# Arduino_mini.net
KiCad netlist of a schematic drawn in Altium Designer
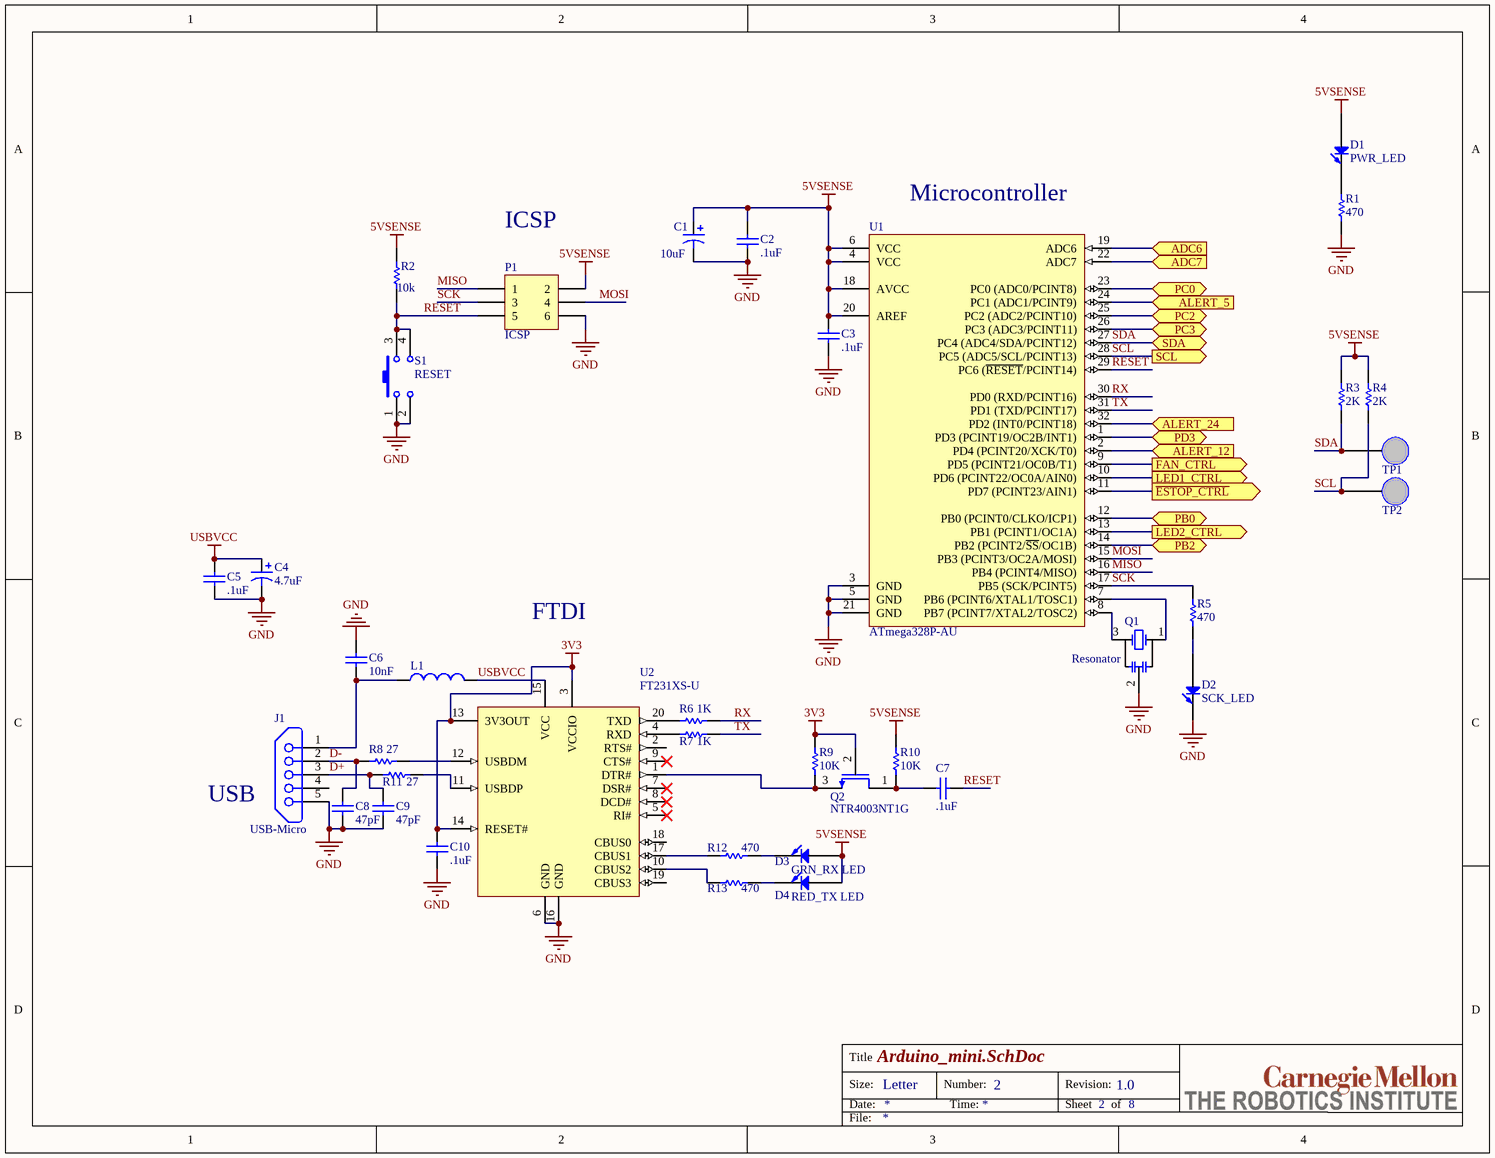
[diagram p0: Arduino_mini.SchDoc]

(export (version "E")
  (design (tool "Eeschema 10.0.6"))
  (components
    (comp (ref "C1")
      (value "10uF")
      (footprint "CAPC2012N")
      (description "Polarized Capacitor (Radial)")
      (fields
        (field (name "MANUFACTURER") "AVX Corporation")
        (field (name "MANUFACTURER PART NUMBER") "TACL106M010RTA")
        (field (name "PUBLISHER") "Altium Limited")
      )
      (libsource (lib "Miscellaneous Devices") (part "Cap Pol1"))
    )
    (comp (ref "C2")
      (value ".1uF")
      (footprint "CAPC1608N")
      (description "Capacitor (Semiconductor SIM Model)")
      (fields
        (field (name "MANUFACTURER") "Murata Electronics North America")
        (field (name "MANUFACTURER PART NUMBER") "GRM188R71C104KA01D")
        (field (name "PUBLISHER") "Altium Limited")
      )
      (libsource (lib "Miscellaneous Devices") (part "Cap Semi"))
    )
    (comp (ref "C3")
      (value ".1uF")
      (footprint "CAPC1608N")
      (description "Capacitor (Semiconductor SIM Model)")
      (fields
        (field (name "MANUFACTURER") "Murata Electronics North America")
        (field (name "MANUFACTURER PART NUMBER") "GRM188R71C104KA01D")
        (field (name "PUBLISHER") "Altium Limited")
      )
      (libsource (lib "Miscellaneous Devices") (part "Cap Semi"))
    )
    (comp (ref "C4")
      (value "4.7uF")
      (footprint "CAPC2012N")
      (description "Polarized Capacitor (Radial)")
      (fields
        (field (name "MANUFACTURER") "AVX Corporation")
        (field (name "MANUFACTURER PART NUMBER") "TACL106M010RTA")
        (field (name "PUBLISHER") "Altium Limited")
      )
      (libsource (lib "Miscellaneous Devices") (part "Cap Pol1"))
    )
    (comp (ref "C5")
      (value ".1uF")
      (footprint "CAPC1608N")
      (description "Capacitor (Semiconductor SIM Model)")
      (fields
        (field (name "MANUFACTURER") "Murata Electronics North America")
        (field (name "MANUFACTURER PART NUMBER") "GRM188R71C104KA01D")
        (field (name "PUBLISHER") "Altium Limited")
      )
      (libsource (lib "Miscellaneous Devices") (part "Cap Semi"))
    )
    (comp (ref "C6")
      (value "10nF")
      (footprint "CAPC1608N")
      (description "Capacitor (Semiconductor SIM Model)")
      (fields
        (field (name "MANUFACTURER") "Murata Electronics North America")
        (field (name "MANUFACTURER PART NUMBER") "GRM188R71C104KA01D")
        (field (name "PUBLISHER") "Altium Limited")
      )
      (libsource (lib "Miscellaneous Devices") (part "Cap Semi"))
    )
    (comp (ref "C7")
      (value ".1uF")
      (footprint "CAPC1608N")
      (description "Capacitor (Semiconductor SIM Model)")
      (fields
        (field (name "MANUFACTURER") "Murata Electronics North America")
        (field (name "MANUFACTURER PART NUMBER") "GRM188R71C104KA01D")
        (field (name "PUBLISHER") "Altium Limited")
      )
      (libsource (lib "Miscellaneous Devices") (part "Cap Semi"))
    )
    (comp (ref "C8")
      (value "47pF")
      (footprint "CAPC1608N")
      (description "Capacitor (Semiconductor SIM Model)")
      (fields
        (field (name "MANUFACTURER") "Murata Electronics North America")
        (field (name "MANUFACTURER PART NUMBER") "GRM188R71C104KA01D")
        (field (name "PUBLISHER") "Altium Limited")
      )
      (libsource (lib "Miscellaneous Devices") (part "Cap Semi"))
    )
    (comp (ref "C9")
      (value "47pF")
      (footprint "CAPC1608N")
      (description "Capacitor (Semiconductor SIM Model)")
      (fields
        (field (name "MANUFACTURER") "Murata Electronics North America")
        (field (name "MANUFACTURER PART NUMBER") "GRM188R71C104KA01D")
        (field (name "PUBLISHER") "Altium Limited")
      )
      (libsource (lib "Miscellaneous Devices") (part "Cap Semi"))
    )
    (comp (ref "C10")
      (value ".1uF")
      (footprint "CAPC1608N")
      (description "Capacitor (Semiconductor SIM Model)")
      (fields
        (field (name "MANUFACTURER") "Murata Electronics North America")
        (field (name "MANUFACTURER PART NUMBER") "GRM188R71C104KA01D")
        (field (name "PUBLISHER") "Altium Limited")
      )
      (libsource (lib "Miscellaneous Devices") (part "Cap Semi"))
    )
    (comp (ref "D1")
      (value "PWR_LED")
      (footprint "common:0603 - LED")
      (description "Green LED")
      (fields
        (field (name "MANUFACTURER") "Lite-On Inc.")
        (field (name "MANUFACTURER PART NUMBER") "LTST-C191TGKT")
      )
      (libsource (lib "common") (part "LED0"))
    )
    (comp (ref "D2")
      (value "SCK_LED")
      (footprint "common:0603 - LED")
      (description "Green LED")
      (fields
        (field (name "MANUFACTURER") "Lite-On Inc.")
        (field (name "MANUFACTURER PART NUMBER") "LTST-C191TBKT")
      )
      (libsource (lib "common") (part "LED0"))
    )
    (comp (ref "D3")
      (value "GRN_RX LED")
      (footprint "common:0603 - LED")
      (description "Green LED")
      (fields
        (field (name "MANUFACTURER") "Lite-On Inc")
        (field (name "MANUFACTURER PART NUMBER") "LTST-C191TGKT")
        (field (name "PUBLISHER") "Altium Limited")
      )
      (libsource (lib "common") (part "LED0"))
    )
    (comp (ref "D4")
      (value "RED_TX LED")
      (footprint "common:0603 - LED")
      (description "led")
      (fields
        (field (name "MANUFACTURER") "Lite-On Inc")
        (field (name "MANUFACTURER PART NUMBER") "LTST-C191KRKT")
        (field (name "PUBLISHER") "Altium Limited")
      )
      (libsource (lib "common") (part "LED0"))
    )
    (comp (ref "J1")
      (value "USB-Micro")
      (footprint "USB-Micro Type B")
      (description "USB-Micro Type B")
      (fields
        (field (name "MANUFACTURER") "Molex Inc")
        (field (name "MANUFACTURER PART NUMBER") "0675031020")
        (field (name "PUBLISHER") "Altium Limited")
      )
      (libsource (lib "common") (part "USB-Micro"))
    )
    (comp (ref "L1")
      (value "Ferrite Bead, USB_PWR")
      (footprint "INDC2012N")
      (description "Inductor")
      (fields
        (field (name "MANUFACTURER") "Laird-Signal Integrity Products")
        (field (name "MANUFACTURER PART NUMBER") "MI0805K400R-10")
        (field (name "PUBLISHER") "Altium Limited")
      )
      (libsource (lib "Miscellaneous Devices") (part "Inductor"))
    )
    (comp (ref "P1")
      (value "ICSP")
      (footprint "MHDR2X3-LOCK")
      (description "Header, 3-Pin, Dual row")
      (fields
        (field (name "MANUFACTURER") "Sullins Connector Solutions")
        (field (name "MANUFACTURER PART NUMBER") "LPPB032CFFN-RC")
      )
      (libsource (lib "Miscellaneous Connectors") (part "MHDR2X3"))
    )
    (comp (ref "Q1")
      (value "Resonator")
      (footprint "Resonator")
      (fields
        (field (name "MANUFACTURER") "Murata Electronics North America")
        (field (name "MANUFACTURER PART NUMBER") "CSTCE16M0V53-R0")
      )
      (libsource (lib "common") (part "Resonator"))
    )
    (comp (ref "Q2")
      (value "NTR4003NT1G")
      (footprint "SOT-23")
      (description "MOSFET N-CH 30V 500MA SOT-23")
      (fields (field (name "MANUFACTURER") "ON Semiconductor"))
      (libsource (lib "common") (part "NTR4003NT1G"))
    )
    (comp (ref "R1")
      (value "470")
      (footprint "RESC1608N")
      (description "Resistor")
      (fields
        (field (name "MANUFACTURER") "Rohm Semiconductor")
        (field (name "MANUFACTURER PART NUMBER") "MCR03ERTJ471")
        (field (name "PUBLISHER") "Altium Limited")
      )
      (libsource (lib "Miscellaneous Devices") (part "Res1"))
    )
    (comp (ref "R2")
      (value "10k")
      (footprint "RESC1608N")
      (description "Resistor")
      (fields
        (field (name "MANUFACTURER") "Yageo")
        (field (name "MANUFACTURER PART NUMBER") "RC0603JR-0710KL")
        (field (name "PUBLISHER") "Altium Limited")
      )
      (libsource (lib "Miscellaneous Devices") (part "Res1"))
    )
    (comp (ref "R3")
      (value "2K")
      (footprint "RESC1608N")
      (description "Resistor")
      (fields
        (field (name "MANUFACTURER") "Rohm Semiconductor")
        (field (name "MANUFACTURER PART NUMBER") "MCR03ERTJ471")
        (field (name "PUBLISHER") "Altium Limited")
      )
      (libsource (lib "Miscellaneous Devices") (part "Res1"))
    )
    (comp (ref "R4")
      (value "2K")
      (footprint "RESC1608N")
      (description "Resistor")
      (fields
        (field (name "MANUFACTURER") "Rohm Semiconductor")
        (field (name "MANUFACTURER PART NUMBER") "MCR03ERTJ471")
        (field (name "PUBLISHER") "Altium Limited")
      )
      (libsource (lib "Miscellaneous Devices") (part "Res1"))
    )
    (comp (ref "R5")
      (value "470")
      (footprint "RESC1608N")
      (description "Resistor")
      (fields
        (field (name "MANUFACTURER") "Rohm Semiconductor")
        (field (name "MANUFACTURER PART NUMBER") "MCR03ERTJ471")
        (field (name "PUBLISHER") "Altium Limited")
      )
      (libsource (lib "Miscellaneous Devices") (part "Res1"))
    )
    (comp (ref "R6")
      (value "1K")
      (footprint "RESC1608N")
      (description "Resistor")
      (fields
        (field (name "MANUFACTURER") "Rohm Semiconductor")
        (field (name "MANUFACTURER PART NUMBER") "MCR03ERTJ471")
        (field (name "PUBLISHER") "Altium Limited")
      )
      (libsource (lib "Miscellaneous Devices") (part "Res1"))
    )
    (comp (ref "R7")
      (value "1K")
      (footprint "RESC1608N")
      (description "Resistor")
      (fields
        (field (name "MANUFACTURER") "Rohm Semiconductor")
        (field (name "MANUFACTURER PART NUMBER") "MCR03ERTJ471")
        (field (name "PUBLISHER") "Altium Limited")
      )
      (libsource (lib "Miscellaneous Devices") (part "Res1"))
    )
    (comp (ref "R8")
      (value "27")
      (footprint "RESC1608N")
      (description "Resistor")
      (fields
        (field (name "MANUFACTURER") "Rohm Semiconductor")
        (field (name "MANUFACTURER PART NUMBER") "MCR03ERTJ471")
        (field (name "PUBLISHER") "Altium Limited")
      )
      (libsource (lib "Miscellaneous Devices") (part "Res1"))
    )
    (comp (ref "R9")
      (value "10K")
      (footprint "RESC1608N")
      (description "Resistor")
      (fields
        (field (name "MANUFACTURER") "Rohm Semiconductor")
        (field (name "MANUFACTURER PART NUMBER") "MCR03ERTJ471")
        (field (name "PUBLISHER") "Altium Limited")
      )
      (libsource (lib "Miscellaneous Devices") (part "Res1"))
    )
    (comp (ref "R10")
      (value "10K")
      (footprint "RESC1608N")
      (description "Resistor")
      (fields
        (field (name "MANUFACTURER") "Rohm Semiconductor")
        (field (name "MANUFACTURER PART NUMBER") "MCR03ERTJ471")
        (field (name "PUBLISHER") "Altium Limited")
      )
      (libsource (lib "Miscellaneous Devices") (part "Res1"))
    )
    (comp (ref "R11")
      (value "27")
      (footprint "RESC1608N")
      (description "Resistor")
      (fields
        (field (name "MANUFACTURER") "Rohm Semiconductor")
        (field (name "MANUFACTURER PART NUMBER") "MCR03ERTJ471")
        (field (name "PUBLISHER") "Altium Limited")
      )
      (libsource (lib "Miscellaneous Devices") (part "Res1"))
    )
    (comp (ref "R12")
      (value "470")
      (footprint "RESC1608N")
      (description "Resistor")
      (fields
        (field (name "MANUFACTURER") "Rohm Semiconductor")
        (field (name "MANUFACTURER PART NUMBER") "MCR03ERTJ471")
        (field (name "PUBLISHER") "Altium Limited")
      )
      (libsource (lib "Miscellaneous Devices") (part "Res1"))
    )
    (comp (ref "R13")
      (value "470")
      (footprint "RESC1608N")
      (description "Resistor")
      (fields
        (field (name "MANUFACTURER") "Rohm Semiconductor")
        (field (name "MANUFACTURER PART NUMBER") "MCR03ERTJ471")
        (field (name "PUBLISHER") "Altium Limited")
      )
      (libsource (lib "Miscellaneous Devices") (part "Res1"))
    )
    (comp (ref "S1")
      (value "RESET")
      (footprint "PushBtn-Tiny")
      (description "Switch")
      (fields
        (field (name "MANUFACTURER") "C&K Components")
        (field (name "MANUFACTURER PART NUMBER") "PTS525SM15SMTR2 LFS")
        (field (name "PUBLISHER") "Altium Limited")
      )
      (libsource (lib "common") (part "SW-PB"))
    )
    (comp (ref "TP1")
      (value "SDA")
      (footprint "TestPoint")
      (description "Test Point")
      (libsource (lib "common") (part "Ring_Terminal"))
    )
    (comp (ref "TP2")
      (value "SCL")
      (footprint "TestPoint")
      (description "Test Point")
      (libsource (lib "common") (part "Ring_Terminal"))
    )
    (comp (ref "U1")
      (value "ATmega328P-AU")
      (footprint "32A_M")
      (fields (field (name "PUBLISHER") "Altium Limited"))
      (libsource (lib "Atmel Microcontroller 8-Bit megaAVR") (part "ATmega328P-AU"))
    )
    (comp (ref "U2")
      (value "FT231XS-U")
      (footprint "SSOP-20_N")
      (description "IC USB SERIAL FULL UART 20SSOP")
      (fields (field (name "MANUFACTURER") "FTDI"))
      (libsource (lib "FTDI FT-X Series") (part "FT231XS-U"))
    )
  )
  (nets
    (net (code "1") (name "/ADC6") (class "Default")
      (node (ref "U1") (pin "19") (pinfunction "ADC6_19") (pintype "input"))
    )
    (net (code "2") (name "/ADC7") (class "Default")
      (node (ref "U1") (pin "22") (pinfunction "ADC7_22") (pintype "input"))
    )
    (net (code "3") (name "/ALERT_5") (class "Default")
      (node (ref "U1") (pin "24") (pinfunction "PC1_(ADC1/PCINT9)_24") (pintype "bidirectional"))
    )
    (net (code "4") (name "/ALERT_12") (class "Default")
      (node (ref "U1") (pin "2") (pinfunction "PD4_(PCINT20/XCK/T0)_2") (pintype "bidirectional"))
    )
    (net (code "5") (name "/ALERT_24") (class "Default")
      (node (ref "U1") (pin "32") (pinfunction "PD2_(INT0/PCINT18)_32") (pintype "bidirectional"))
    )
    (net (code "6") (name "/D+") (class "Default")
      (node (ref "C9") (pin "2") (pinfunction "2_2") (pintype "passive"))
      (node (ref "J1") (pin "3") (pinfunction "D+_3") (pintype "passive"))
      (node (ref "R11") (pin "2") (pinfunction "2_2") (pintype "passive"))
    )
    (net (code "7") (name "/D-") (class "Default")
      (node (ref "C8") (pin "2") (pinfunction "2_2") (pintype "passive"))
      (node (ref "J1") (pin "2") (pinfunction "D-_2") (pintype "passive"))
      (node (ref "R8") (pin "2") (pinfunction "2_2") (pintype "passive"))
    )
    (net (code "8") (name "/FAN_CTRL") (class "Default")
      (node (ref "U1") (pin "9") (pinfunction "PD5_(PCINT21/OC0B/T1)_9") (pintype "bidirectional"))
    )
    (net (code "9") (name "/LED1_CTRL") (class "Default")
      (node (ref "U1") (pin "10") (pinfunction "PD6_(PCINT22/OC0A/AIN0)_10") (pintype "bidirectional"))
    )
    (net (code "10") (name "/LED2_CTRL") (class "Default")
      (node (ref "U1") (pin "13") (pinfunction "PB1_(PCINT1/OC1A)_13") (pintype "bidirectional"))
    )
    (net (code "11") (name "/MISO") (class "Default")
      (node (ref "P1") (pin "1") (pinfunction "1_1") (pintype "passive"))
      (node (ref "U1") (pin "16") (pinfunction "PB4_(PCINT4/MISO)_16") (pintype "bidirectional"))
    )
    (net (code "12") (name "/MOSI") (class "Default")
      (node (ref "P1") (pin "4") (pinfunction "4_4") (pintype "passive"))
      (node (ref "U1") (pin "15") (pinfunction "PB3_(PCINT3/OC2A/MOSI)_15") (pintype "bidirectional"))
    )
    (net (code "13") (name "/PB0") (class "Default")
      (node (ref "U1") (pin "12") (pinfunction "PB0_(PCINT0/CLKO/ICP1)_12") (pintype "bidirectional"))
    )
    (net (code "14") (name "/PB2") (class "Default")
      (node (ref "U1") (pin "14") (pinfunction "PB2_(PCINT2/~{SS}/OC1B)_14") (pintype "bidirectional"))
    )
    (net (code "15") (name "/PC0") (class "Default")
      (node (ref "U1") (pin "23") (pinfunction "PC0_(ADC0/PCINT8)_23") (pintype "bidirectional"))
    )
    (net (code "16") (name "/PC2") (class "Default")
      (node (ref "U1") (pin "25") (pinfunction "PC2_(ADC2/PCINT10)_25") (pintype "bidirectional"))
    )
    (net (code "17") (name "/PC3") (class "Default")
      (node (ref "U1") (pin "26") (pinfunction "PC3_(ADC3/PCINT11)_26") (pintype "bidirectional"))
    )
    (net (code "18") (name "/PD3") (class "Default")
      (node (ref "U1") (pin "1") (pinfunction "PD3_(PCINT19/OC2B/INT1)_1") (pintype "bidirectional"))
    )
    (net (code "19") (name "/RESET") (class "Default")
      (node (ref "C7") (pin "2") (pinfunction "2_2") (pintype "passive"))
      (node (ref "P1") (pin "5") (pinfunction "5_5") (pintype "passive"))
      (node (ref "R2") (pin "1") (pinfunction "1_1") (pintype "passive"))
      (node (ref "S1") (pin "3") (pinfunction "3_3") (pintype "passive"))
      (node (ref "S1") (pin "4") (pinfunction "4_4") (pintype "passive"))
      (node (ref "U1") (pin "29") (pinfunction "PC6_(~{RESET}/PCINT14)_29") (pintype "bidirectional"))
    )
    (net (code "20") (name "/RX") (class "Default")
      (node (ref "R6") (pin "1") (pinfunction "1_1") (pintype "passive"))
      (node (ref "U1") (pin "30") (pinfunction "PD0_(RXD/PCINT16)_30") (pintype "bidirectional"))
    )
    (net (code "21") (name "/SCK") (class "Default")
      (node (ref "P1") (pin "3") (pinfunction "3_3") (pintype "passive"))
      (node (ref "R5") (pin "2") (pinfunction "2_2") (pintype "passive"))
      (node (ref "U1") (pin "17") (pinfunction "PB5_(SCK/PCINT5)_17") (pintype "bidirectional"))
    )
    (net (code "22") (name "/SCL") (class "Default")
      (node (ref "R4") (pin "1") (pinfunction "1_1") (pintype "passive"))
      (node (ref "TP2") (pin "1") (pinfunction "1_1") (pintype "passive"))
      (node (ref "U1") (pin "28") (pinfunction "PC5_(ADC5/SCL/PCINT13)_28") (pintype "bidirectional"))
    )
    (net (code "23") (name "/SDA") (class "Default")
      (node (ref "R3") (pin "1") (pinfunction "1_1") (pintype "passive"))
      (node (ref "TP1") (pin "1") (pinfunction "1_1") (pintype "passive"))
      (node (ref "U1") (pin "27") (pinfunction "PC4_(ADC4/SDA/PCINT12)_27") (pintype "bidirectional"))
    )
    (net (code "24") (name "/TX") (class "Default")
      (node (ref "R7") (pin "1") (pinfunction "1_1") (pintype "passive"))
      (node (ref "U1") (pin "31") (pinfunction "PD1_(TXD/PCINT17)_31") (pintype "bidirectional"))
    )
    (net (code "25") (name "/~{ESTOP_CTRL}") (class "Default")
      (node (ref "U1") (pin "11") (pinfunction "PD7_(PCINT23/AIN1)_11") (pintype "bidirectional"))
    )
    (net (code "26") (name "3V3") (class "Default")
      (node (ref "C10") (pin "2") (pinfunction "2_2") (pintype "passive"))
      (node (ref "Q2") (pin "2") (pinfunction "2_2") (pintype "passive"))
      (node (ref "R9") (pin "2") (pinfunction "2_2") (pintype "passive"))
      (node (ref "U2") (pin "13") (pinfunction "3V3OUT_13") (pintype "power_in"))
      (node (ref "U2") (pin "14") (pinfunction "RESET#_14") (pintype "input"))
      (node (ref "U2") (pin "3") (pinfunction "VCCIO_3") (pintype "power_in"))
    )
    (net (code "27") (name "5VSENSE") (class "Default")
      (node (ref "C1") (pin "1") (pinfunction "1_1") (pintype "passive"))
      (node (ref "C2") (pin "1") (pinfunction "1_1") (pintype "passive"))
      (node (ref "C3") (pin "1") (pinfunction "1_1") (pintype "passive"))
      (node (ref "D1") (pin "2") (pinfunction "A_2") (pintype "passive"))
      (node (ref "D3") (pin "2") (pinfunction "A_2") (pintype "passive"))
      (node (ref "D4") (pin "2") (pinfunction "A_2") (pintype "passive"))
      (node (ref "P1") (pin "2") (pinfunction "2_2") (pintype "passive"))
      (node (ref "R10") (pin "2") (pinfunction "2_2") (pintype "passive"))
      (node (ref "R2") (pin "2") (pinfunction "2_2") (pintype "passive"))
      (node (ref "R3") (pin "2") (pinfunction "2_2") (pintype "passive"))
      (node (ref "R4") (pin "2") (pinfunction "2_2") (pintype "passive"))
      (node (ref "U1") (pin "18") (pinfunction "AVCC_18") (pintype "power_in"))
      (node (ref "U1") (pin "20") (pinfunction "AREF_20") (pintype "passive"))
      (node (ref "U1") (pin "4") (pinfunction "VCC_4") (pintype "power_in"))
      (node (ref "U1") (pin "6") (pinfunction "VCC_6") (pintype "power_in"))
    )
    (net (code "28") (name "GND") (class "Default")
      (node (ref "C1") (pin "2") (pinfunction "2_2") (pintype "passive"))
      (node (ref "C10") (pin "1") (pinfunction "1_1") (pintype "passive"))
      (node (ref "C2") (pin "2") (pinfunction "2_2") (pintype "passive"))
      (node (ref "C3") (pin "2") (pinfunction "2_2") (pintype "passive"))
      (node (ref "C4") (pin "2") (pinfunction "2_2") (pintype "passive"))
      (node (ref "C5") (pin "2") (pinfunction "2_2") (pintype "passive"))
      (node (ref "C6") (pin "2") (pinfunction "2_2") (pintype "passive"))
      (node (ref "C8") (pin "1") (pinfunction "1_1") (pintype "passive"))
      (node (ref "C9") (pin "1") (pinfunction "1_1") (pintype "passive"))
      (node (ref "D2") (pin "1") (pinfunction "K_1") (pintype "passive"))
      (node (ref "J1") (pin "5") (pinfunction "GND_5") (pintype "passive"))
      (node (ref "P1") (pin "6") (pinfunction "6_6") (pintype "passive"))
      (node (ref "Q1") (pin "2") (pinfunction "GND_2") (pintype "passive"))
      (node (ref "R1") (pin "1") (pinfunction "1_1") (pintype "passive"))
      (node (ref "S1") (pin "1") (pinfunction "1_1") (pintype "passive"))
      (node (ref "S1") (pin "2") (pinfunction "2_2") (pintype "passive"))
      (node (ref "U1") (pin "21") (pinfunction "GND_21") (pintype "power_in"))
      (node (ref "U1") (pin "3") (pinfunction "GND_3") (pintype "power_in"))
      (node (ref "U1") (pin "5") (pinfunction "GND_5") (pintype "power_in"))
      (node (ref "U2") (pin "16") (pinfunction "GND_16") (pintype "power_in"))
      (node (ref "U2") (pin "6") (pinfunction "GND_6") (pintype "power_in"))
    )
    (net (code "29") (name "Net-(C7-Pad1)") (class "Default")
      (node (ref "C7") (pin "1") (pinfunction "1_1") (pintype "passive"))
      (node (ref "Q2") (pin "1") (pinfunction "1_1") (pintype "passive"))
      (node (ref "R10") (pin "1") (pinfunction "1_1") (pintype "passive"))
    )
    (net (code "30") (name "Net-(D1-K)") (class "Default")
      (node (ref "D1") (pin "1") (pinfunction "K_1") (pintype "passive"))
      (node (ref "R1") (pin "2") (pinfunction "2_2") (pintype "passive"))
    )
    (net (code "31") (name "Net-(D2-A)") (class "Default")
      (node (ref "D2") (pin "2") (pinfunction "A_2") (pintype "passive"))
      (node (ref "R5") (pin "1") (pinfunction "1_1") (pintype "passive"))
    )
    (net (code "32") (name "Net-(D3-K)") (class "Default")
      (node (ref "D3") (pin "1") (pinfunction "K_1") (pintype "passive"))
      (node (ref "R12") (pin "1") (pinfunction "1_1") (pintype "passive"))
    )
    (net (code "33") (name "Net-(D4-K)") (class "Default")
      (node (ref "D4") (pin "1") (pinfunction "K_1") (pintype "passive"))
      (node (ref "R13") (pin "1") (pinfunction "1_1") (pintype "passive"))
    )
    (net (code "34") (name "Net-(J1-V_BUS)") (class "Default")
      (node (ref "C6") (pin "1") (pinfunction "1_1") (pintype "passive"))
      (node (ref "J1") (pin "1") (pinfunction "V_BUS_1") (pintype "passive"))
      (node (ref "L1") (pin "1") (pinfunction "1_1") (pintype "passive"))
    )
    (net (code "35") (name "Net-(Q1-OSC1)") (class "Default")
      (node (ref "Q1") (pin "1") (pinfunction "OSC1_1") (pintype "passive"))
      (node (ref "U1") (pin "7") (pinfunction "PB6_(PCINT6/XTAL1/TOSC1)_7") (pintype "bidirectional"))
    )
    (net (code "36") (name "Net-(Q1-OSC2)") (class "Default")
      (node (ref "Q1") (pin "3") (pinfunction "OSC2_3") (pintype "passive"))
      (node (ref "U1") (pin "8") (pinfunction "PB7_(PCINT7/XTAL2/TOSC2)_8") (pintype "bidirectional"))
    )
    (net (code "37") (name "Net-(U2-CBUS1)") (class "Default")
      (node (ref "R12") (pin "2") (pinfunction "2_2") (pintype "passive"))
      (node (ref "U2") (pin "17") (pinfunction "CBUS1_17") (pintype "bidirectional"))
    )
    (net (code "38") (name "Net-(U2-CBUS2)") (class "Default")
      (node (ref "R13") (pin "2") (pinfunction "2_2") (pintype "passive"))
      (node (ref "U2") (pin "10") (pinfunction "CBUS2_10") (pintype "bidirectional"))
    )
    (net (code "39") (name "Net-(U2-DTR#)") (class "Default")
      (node (ref "Q2") (pin "3") (pinfunction "3_3") (pintype "passive"))
      (node (ref "R9") (pin "1") (pinfunction "1_1") (pintype "passive"))
      (node (ref "U2") (pin "1") (pinfunction "DTR#_1") (pintype "output"))
    )
    (net (code "40") (name "Net-(U2-RXD)") (class "Default")
      (node (ref "R7") (pin "2") (pinfunction "2_2") (pintype "passive"))
      (node (ref "U2") (pin "4") (pinfunction "RXD_4") (pintype "input"))
    )
    (net (code "41") (name "Net-(U2-TXD)") (class "Default")
      (node (ref "R6") (pin "2") (pinfunction "2_2") (pintype "passive"))
      (node (ref "U2") (pin "20") (pinfunction "TXD_20") (pintype "output"))
    )
    (net (code "42") (name "Net-(U2-USBDM)") (class "Default")
      (node (ref "R8") (pin "1") (pinfunction "1_1") (pintype "passive"))
      (node (ref "U2") (pin "12") (pinfunction "USBDM_12") (pintype "input"))
    )
    (net (code "43") (name "Net-(U2-USBDP)") (class "Default")
      (node (ref "R11") (pin "1") (pinfunction "1_1") (pintype "passive"))
      (node (ref "U2") (pin "11") (pinfunction "USBDP_11") (pintype "input"))
    )
    (net (code "44") (name "USBVCC") (class "Default")
      (node (ref "C4") (pin "1") (pinfunction "1_1") (pintype "passive"))
      (node (ref "C5") (pin "1") (pinfunction "1_1") (pintype "passive"))
      (node (ref "L1") (pin "2") (pinfunction "2_2") (pintype "passive"))
      (node (ref "U2") (pin "15") (pinfunction "VCC_15") (pintype "power_in"))
    )
    (net (code "45") (name "unconnected-(J1-ID-Pad4)") (class "Default")
      (node (ref "J1") (pin "4") (pinfunction "ID_4") (pintype "passive"))
    )
    (net (code "46") (name "unconnected-(U2-CBUS0-Pad18)") (class "Default")
      (node (ref "U2") (pin "18") (pinfunction "CBUS0_18") (pintype "bidirectional"))
    )
    (net (code "47") (name "unconnected-(U2-CBUS3-Pad19)") (class "Default")
      (node (ref "U2") (pin "19") (pinfunction "CBUS3_19") (pintype "bidirectional"))
    )
    (net (code "48") (name "unconnected-(U2-CTS#-Pad9)") (class "Default")
      (node (ref "U2") (pin "9") (pinfunction "CTS#_9") (pintype "input+no_connect"))
    )
    (net (code "49") (name "unconnected-(U2-DCD#-Pad8)") (class "Default")
      (node (ref "U2") (pin "8") (pinfunction "DCD#_8") (pintype "input+no_connect"))
    )
    (net (code "50") (name "unconnected-(U2-DSR#-Pad7)") (class "Default")
      (node (ref "U2") (pin "7") (pinfunction "DSR#_7") (pintype "input+no_connect"))
    )
    (net (code "51") (name "unconnected-(U2-RI#-Pad5)") (class "Default")
      (node (ref "U2") (pin "5") (pinfunction "RI#_5") (pintype "input+no_connect"))
    )
    (net (code "52") (name "unconnected-(U2-RTS#-Pad2)") (class "Default")
      (node (ref "U2") (pin "2") (pinfunction "RTS#_2") (pintype "output"))
    )
  )
)
